# SWD_PROGRAMMER_minimal_modified.net
KiCad netlist of a schematic drawn in EAGLE
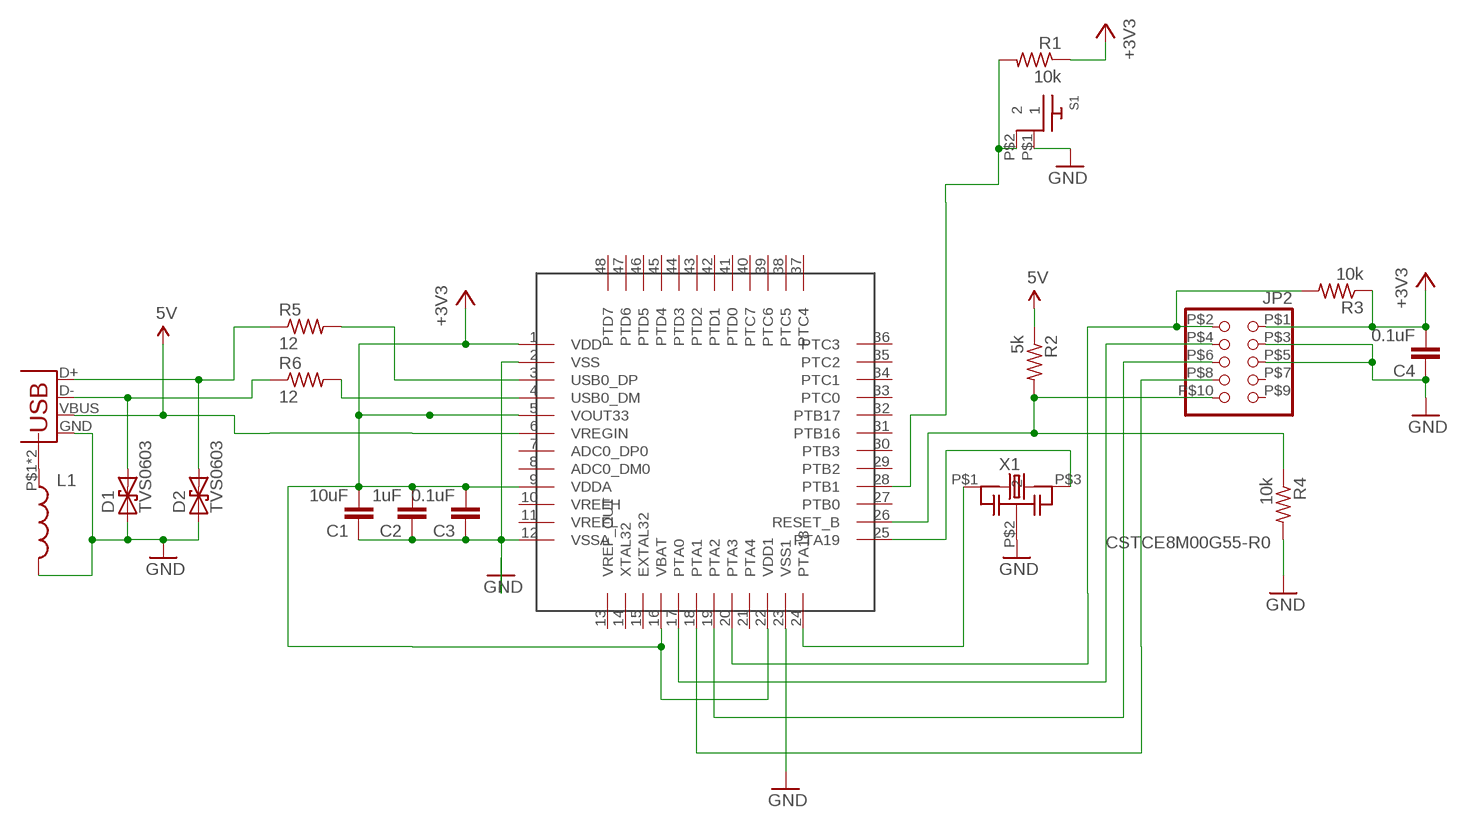
[diagram p0: schematic, sheet 1]

(export (version "E")
  (design (tool "Eeschema 10.0.6"))
  (components
    (comp (ref "C1")
      (value "10uF")
      (footprint "eagle-import:C0805")
      (libsource (lib "eagle-import") (part "RF-C0805"))
    )
    (comp (ref "C2")
      (value "1uF")
      (footprint "eagle-import:C0805")
      (libsource (lib "eagle-import") (part "RF-C0805"))
    )
    (comp (ref "C3")
      (value "0.1uF")
      (footprint "eagle-import:C0805")
      (libsource (lib "eagle-import") (part "RF-C0805"))
    )
    (comp (ref "C4")
      (value "0.1uF")
      (footprint "eagle-import:C0805")
      (libsource (lib "eagle-import") (part "RF-C0805"))
    )
    (comp (ref "D1")
      (value "TVS0603")
      (footprint "eagle-import:0603-RES")
      (libsource (lib "eagle-import") (part "TVS0603"))
    )
    (comp (ref "D2")
      (value "TVS0603")
      (footprint "eagle-import:0603-RES")
      (libsource (lib "eagle-import") (part "TVS0603"))
    )
    (comp (ref "J1")
      (value "USB_B")
      (footprint "eagle-import:USB-B-PTH-VERTICAL")
      (libsource (lib "eagle-import") (part "USB_B"))
    )
    (comp (ref "JP2")
      (value "PINHD-2X5SMALL")
      (footprint "eagle-import:2X5HDR")
      (libsource (lib "eagle-import") (part "PINHD-2X5SMALL"))
    )
    (comp (ref "L1")
      (value "INDUCTOR0603")
      (footprint "eagle-import:0603")
      (libsource (lib "eagle-import") (part "INDUCTOR0603"))
    )
    (comp (ref "R1")
      (value "10k")
      (footprint "eagle-import:RF-C0805")
      (libsource (lib "eagle-import") (part "RF-R0805"))
    )
    (comp (ref "R2")
      (value "5k")
      (footprint "eagle-import:RF-C0805")
      (libsource (lib "eagle-import") (part "RF-R0805"))
    )
    (comp (ref "R3")
      (value "10k")
      (footprint "eagle-import:RF-C0805")
      (libsource (lib "eagle-import") (part "RF-R0805"))
    )
    (comp (ref "R4")
      (value "10k")
      (footprint "eagle-import:RF-C0805")
      (libsource (lib "eagle-import") (part "RF-R0805"))
    )
    (comp (ref "R5")
      (value "12")
      (footprint "eagle-import:RF-C0805")
      (libsource (lib "eagle-import") (part "RF-R0805"))
    )
    (comp (ref "R6")
      (value "12")
      (footprint "eagle-import:RF-C0805")
      (libsource (lib "eagle-import") (part "RF-R0805"))
    )
    (comp (ref "S1")
      (value "RA_BUTTON")
      (footprint "eagle-import:RA_BUTTON")
      (libsource (lib "eagle-import") (part "RA_BUTTON"))
    )
    (comp (ref "U$1")
      (value "KL20_48")
      (footprint "eagle-import:LQFP-48")
      (libsource (lib "eagle-import") (part "KL20_48"))
    )
    (comp (ref "X1")
      (value "CSTCE8M00G55-R0")
      (footprint "eagle-import:CSTCE_G_A")
      (libsource (lib "eagle-import") (part "CSTCE8M00G55-R0"))
    )
  )
  (nets
    (net (code "1") (name "+3V3") (class "Default")
      (node (ref "C1") (pin "2") (pinfunction "2_2") (pintype "passive"))
      (node (ref "C2") (pin "2") (pinfunction "2_2") (pintype "passive"))
      (node (ref "C3") (pin "2") (pinfunction "2_2") (pintype "passive"))
      (node (ref "C4") (pin "2") (pinfunction "2_2") (pintype "passive"))
      (node (ref "JP2") (pin "P$1") (pinfunction "1_P$1") (pintype "passive"))
      (node (ref "R1") (pin "1") (pinfunction "1_1") (pintype "passive"))
      (node (ref "R3") (pin "1") (pinfunction "1_1") (pintype "passive"))
      (node (ref "U$1") (pin "1") (pinfunction "VDD_1") (pintype "bidirectional"))
      (node (ref "U$1") (pin "16") (pinfunction "VBAT_16") (pintype "bidirectional"))
      (node (ref "U$1") (pin "22") (pinfunction "VDD1_22") (pintype "bidirectional"))
      (node (ref "U$1") (pin "5") (pinfunction "VOUT33_5") (pintype "bidirectional"))
      (node (ref "U$1") (pin "9") (pinfunction "VDDA_9") (pintype "bidirectional"))
    )
    (net (code "2") (name "5V") (class "Default")
      (node (ref "J1") (pin "VBUS") (pinfunction "VBUS_VBUS") (pintype "bidirectional"))
      (node (ref "R2") (pin "1") (pinfunction "1_1") (pintype "passive"))
      (node (ref "U$1") (pin "6") (pinfunction "VREGIN_6") (pintype "bidirectional"))
    )
    (net (code "3") (name "GND") (class "Default")
      (node (ref "C1") (pin "1") (pinfunction "1_1") (pintype "passive"))
      (node (ref "C2") (pin "1") (pinfunction "1_1") (pintype "passive"))
      (node (ref "C3") (pin "1") (pinfunction "1_1") (pintype "passive"))
      (node (ref "C4") (pin "1") (pinfunction "1_1") (pintype "passive"))
      (node (ref "D1") (pin "1") (pinfunction "1_1") (pintype "passive"))
      (node (ref "D2") (pin "1") (pinfunction "1_1") (pintype "passive"))
      (node (ref "J1") (pin "GND") (pinfunction "GND_GND") (pintype "bidirectional"))
      (node (ref "JP2") (pin "P$3") (pinfunction "3_P$3") (pintype "passive"))
      (node (ref "JP2") (pin "P$5") (pinfunction "5_P$5") (pintype "passive"))
      (node (ref "L1") (pin "2") (pinfunction "2_2") (pintype "passive"))
      (node (ref "R4") (pin "2") (pinfunction "2_2") (pintype "passive"))
      (node (ref "S1") (pin "P$1") (pinfunction "1_P$1") (pintype "input"))
      (node (ref "U$1") (pin "12") (pinfunction "VSSA_12") (pintype "bidirectional"))
      (node (ref "U$1") (pin "2") (pinfunction "VSS_2") (pintype "bidirectional"))
      (node (ref "U$1") (pin "23") (pinfunction "VSS1_23") (pintype "bidirectional"))
      (node (ref "X1") (pin "P$2") (pinfunction "2_P$2") (pintype "passive"))
    )
    (net (code "4") (name "Net-(D1-Pad2)") (class "Default")
      (node (ref "D1") (pin "2") (pinfunction "2_2") (pintype "passive"))
      (node (ref "J1") (pin "D-") (pinfunction "D-_D-") (pintype "bidirectional"))
      (node (ref "R6") (pin "1") (pinfunction "1_1") (pintype "passive"))
    )
    (net (code "5") (name "Net-(D2-Pad2)") (class "Default")
      (node (ref "D2") (pin "2") (pinfunction "2_2") (pintype "passive"))
      (node (ref "J1") (pin "D+") (pinfunction "D+_D+") (pintype "bidirectional"))
      (node (ref "R5") (pin "1") (pinfunction "1_1") (pintype "passive"))
    )
    (net (code "6") (name "Net-(J1-SHIELD-PadP$1)") (class "Default")
      (node (ref "J1") (pin "P$1") (pinfunction "SHIELD_P$1") (pintype "bidirectional"))
      (node (ref "J1") (pin "P$2") (pinfunction "SHIELD_P$2") (pintype "bidirectional"))
      (node (ref "L1") (pin "1") (pinfunction "1_1") (pintype "passive"))
    )
    (net (code "7") (name "Net-(JP2-2)") (class "Default")
      (node (ref "JP2") (pin "P$2") (pinfunction "2_P$2") (pintype "passive"))
      (node (ref "R3") (pin "2") (pinfunction "2_2") (pintype "passive"))
      (node (ref "U$1") (pin "20") (pinfunction "PTA3_20") (pintype "bidirectional"))
    )
    (net (code "8") (name "Net-(JP2-4)") (class "Default")
      (node (ref "JP2") (pin "P$4") (pinfunction "4_P$4") (pintype "passive"))
      (node (ref "U$1") (pin "17") (pinfunction "PTA0_17") (pintype "bidirectional"))
    )
    (net (code "9") (name "Net-(JP2-6)") (class "Default")
      (node (ref "JP2") (pin "P$6") (pinfunction "6_P$6") (pintype "passive"))
      (node (ref "U$1") (pin "19") (pinfunction "PTA2_19") (pintype "bidirectional"))
    )
    (net (code "10") (name "Net-(JP2-8)") (class "Default")
      (node (ref "JP2") (pin "P$8") (pinfunction "8_P$8") (pintype "passive"))
      (node (ref "U$1") (pin "18") (pinfunction "PTA1_18") (pintype "bidirectional"))
    )
    (net (code "11") (name "Net-(JP2-10)") (class "Default")
      (node (ref "JP2") (pin "P$10") (pinfunction "10_P$10") (pintype "passive"))
      (node (ref "R2") (pin "2") (pinfunction "2_2") (pintype "passive"))
      (node (ref "R4") (pin "1") (pinfunction "1_1") (pintype "passive"))
      (node (ref "U$1") (pin "26") (pinfunction "RESET_B_26") (pintype "bidirectional"))
    )
    (net (code "12") (name "Net-(S1-2)") (class "Default")
      (node (ref "R1") (pin "2") (pinfunction "2_2") (pintype "passive"))
      (node (ref "S1") (pin "P$2") (pinfunction "2_P$2") (pintype "input"))
      (node (ref "U$1") (pin "28") (pinfunction "PTB1_28") (pintype "bidirectional"))
    )
    (net (code "13") (name "Net-(U$1-PTA18)") (class "Default")
      (node (ref "U$1") (pin "24") (pinfunction "PTA18_24") (pintype "bidirectional"))
      (node (ref "X1") (pin "P$1") (pinfunction "1_P$1") (pintype "passive"))
    )
    (net (code "14") (name "Net-(U$1-PTA19)") (class "Default")
      (node (ref "U$1") (pin "25") (pinfunction "PTA19_25") (pintype "bidirectional"))
      (node (ref "X1") (pin "P$3") (pinfunction "3_P$3") (pintype "passive"))
    )
    (net (code "15") (name "Net-(U$1-USB0_DM)") (class "Default")
      (node (ref "R6") (pin "2") (pinfunction "2_2") (pintype "passive"))
      (node (ref "U$1") (pin "4") (pinfunction "USB0_DM_4") (pintype "bidirectional"))
    )
    (net (code "16") (name "Net-(U$1-USB0_DP)") (class "Default")
      (node (ref "R5") (pin "2") (pinfunction "2_2") (pintype "passive"))
      (node (ref "U$1") (pin "3") (pinfunction "USB0_DP_3") (pintype "bidirectional"))
    )
    (net (code "17") (name "unconnected-(JP2-7-PadP$7)") (class "Default")
      (node (ref "JP2") (pin "P$7") (pinfunction "7_P$7") (pintype "passive"))
    )
    (net (code "18") (name "unconnected-(JP2-9-PadP$9)") (class "Default")
      (node (ref "JP2") (pin "P$9") (pinfunction "9_P$9") (pintype "passive"))
    )
    (net (code "19") (name "unconnected-(U$1-ADC0_DM0-Pad8)") (class "Default")
      (node (ref "U$1") (pin "8") (pinfunction "ADC0_DM0_8") (pintype "bidirectional"))
    )
    (net (code "20") (name "unconnected-(U$1-ADC0_DP0-Pad7)") (class "Default")
      (node (ref "U$1") (pin "7") (pinfunction "ADC0_DP0_7") (pintype "bidirectional"))
    )
    (net (code "21") (name "unconnected-(U$1-EXTAL32-Pad15)") (class "Default")
      (node (ref "U$1") (pin "15") (pinfunction "EXTAL32_15") (pintype "bidirectional"))
    )
    (net (code "22") (name "unconnected-(U$1-PTA4-Pad21)") (class "Default")
      (node (ref "U$1") (pin "21") (pinfunction "PTA4_21") (pintype "bidirectional"))
    )
    (net (code "23") (name "unconnected-(U$1-PTB0-Pad27)") (class "Default")
      (node (ref "U$1") (pin "27") (pinfunction "PTB0_27") (pintype "bidirectional"))
    )
    (net (code "24") (name "unconnected-(U$1-PTB2-Pad29)") (class "Default")
      (node (ref "U$1") (pin "29") (pinfunction "PTB2_29") (pintype "bidirectional"))
    )
    (net (code "25") (name "unconnected-(U$1-PTB3-Pad30)") (class "Default")
      (node (ref "U$1") (pin "30") (pinfunction "PTB3_30") (pintype "bidirectional"))
    )
    (net (code "26") (name "unconnected-(U$1-PTB16-Pad31)") (class "Default")
      (node (ref "U$1") (pin "31") (pinfunction "PTB16_31") (pintype "bidirectional"))
    )
    (net (code "27") (name "unconnected-(U$1-PTB17-Pad32)") (class "Default")
      (node (ref "U$1") (pin "32") (pinfunction "PTB17_32") (pintype "bidirectional"))
    )
    (net (code "28") (name "unconnected-(U$1-PTC0-Pad33)") (class "Default")
      (node (ref "U$1") (pin "33") (pinfunction "PTC0_33") (pintype "bidirectional"))
    )
    (net (code "29") (name "unconnected-(U$1-PTC1-Pad34)") (class "Default")
      (node (ref "U$1") (pin "34") (pinfunction "PTC1_34") (pintype "bidirectional"))
    )
    (net (code "30") (name "unconnected-(U$1-PTC2-Pad35)") (class "Default")
      (node (ref "U$1") (pin "35") (pinfunction "PTC2_35") (pintype "bidirectional"))
    )
    (net (code "31") (name "unconnected-(U$1-PTC3-Pad36)") (class "Default")
      (node (ref "U$1") (pin "36") (pinfunction "PTC3_36") (pintype "bidirectional"))
    )
    (net (code "32") (name "unconnected-(U$1-PTC4-Pad37)") (class "Default")
      (node (ref "U$1") (pin "37") (pinfunction "PTC4_37") (pintype "bidirectional"))
    )
    (net (code "33") (name "unconnected-(U$1-PTC5-Pad38)") (class "Default")
      (node (ref "U$1") (pin "38") (pinfunction "PTC5_38") (pintype "bidirectional"))
    )
    (net (code "34") (name "unconnected-(U$1-PTC6-Pad39)") (class "Default")
      (node (ref "U$1") (pin "39") (pinfunction "PTC6_39") (pintype "bidirectional"))
    )
    (net (code "35") (name "unconnected-(U$1-PTC7-Pad40)") (class "Default")
      (node (ref "U$1") (pin "40") (pinfunction "PTC7_40") (pintype "bidirectional"))
    )
    (net (code "36") (name "unconnected-(U$1-PTD0-Pad41)") (class "Default")
      (node (ref "U$1") (pin "41") (pinfunction "PTD0_41") (pintype "bidirectional"))
    )
    (net (code "37") (name "unconnected-(U$1-PTD1-Pad42)") (class "Default")
      (node (ref "U$1") (pin "42") (pinfunction "PTD1_42") (pintype "bidirectional"))
    )
    (net (code "38") (name "unconnected-(U$1-PTD2-Pad43)") (class "Default")
      (node (ref "U$1") (pin "43") (pinfunction "PTD2_43") (pintype "bidirectional"))
    )
    (net (code "39") (name "unconnected-(U$1-PTD3-Pad44)") (class "Default")
      (node (ref "U$1") (pin "44") (pinfunction "PTD3_44") (pintype "bidirectional"))
    )
    (net (code "40") (name "unconnected-(U$1-PTD4-Pad45)") (class "Default")
      (node (ref "U$1") (pin "45") (pinfunction "PTD4_45") (pintype "bidirectional"))
    )
    (net (code "41") (name "unconnected-(U$1-PTD5-Pad46)") (class "Default")
      (node (ref "U$1") (pin "46") (pinfunction "PTD5_46") (pintype "bidirectional"))
    )
    (net (code "42") (name "unconnected-(U$1-PTD6-Pad47)") (class "Default")
      (node (ref "U$1") (pin "47") (pinfunction "PTD6_47") (pintype "bidirectional"))
    )
    (net (code "43") (name "unconnected-(U$1-PTD7-Pad48)") (class "Default")
      (node (ref "U$1") (pin "48") (pinfunction "PTD7_48") (pintype "bidirectional"))
    )
    (net (code "44") (name "unconnected-(U$1-VREFH-Pad10)") (class "Default")
      (node (ref "U$1") (pin "10") (pinfunction "VREFH_10") (pintype "bidirectional"))
    )
    (net (code "45") (name "unconnected-(U$1-VREFL-Pad11)") (class "Default")
      (node (ref "U$1") (pin "11") (pinfunction "VREFL_11") (pintype "bidirectional"))
    )
    (net (code "46") (name "unconnected-(U$1-VREF_OUT-Pad13)") (class "Default")
      (node (ref "U$1") (pin "13") (pinfunction "VREF_OUT_13") (pintype "bidirectional"))
    )
    (net (code "47") (name "unconnected-(U$1-XTAL32-Pad14)") (class "Default")
      (node (ref "U$1") (pin "14") (pinfunction "XTAL32_14") (pintype "bidirectional"))
    )
  )
)
